# Power_noise.net
KiCad netlist of a schematic drawn in EAGLE
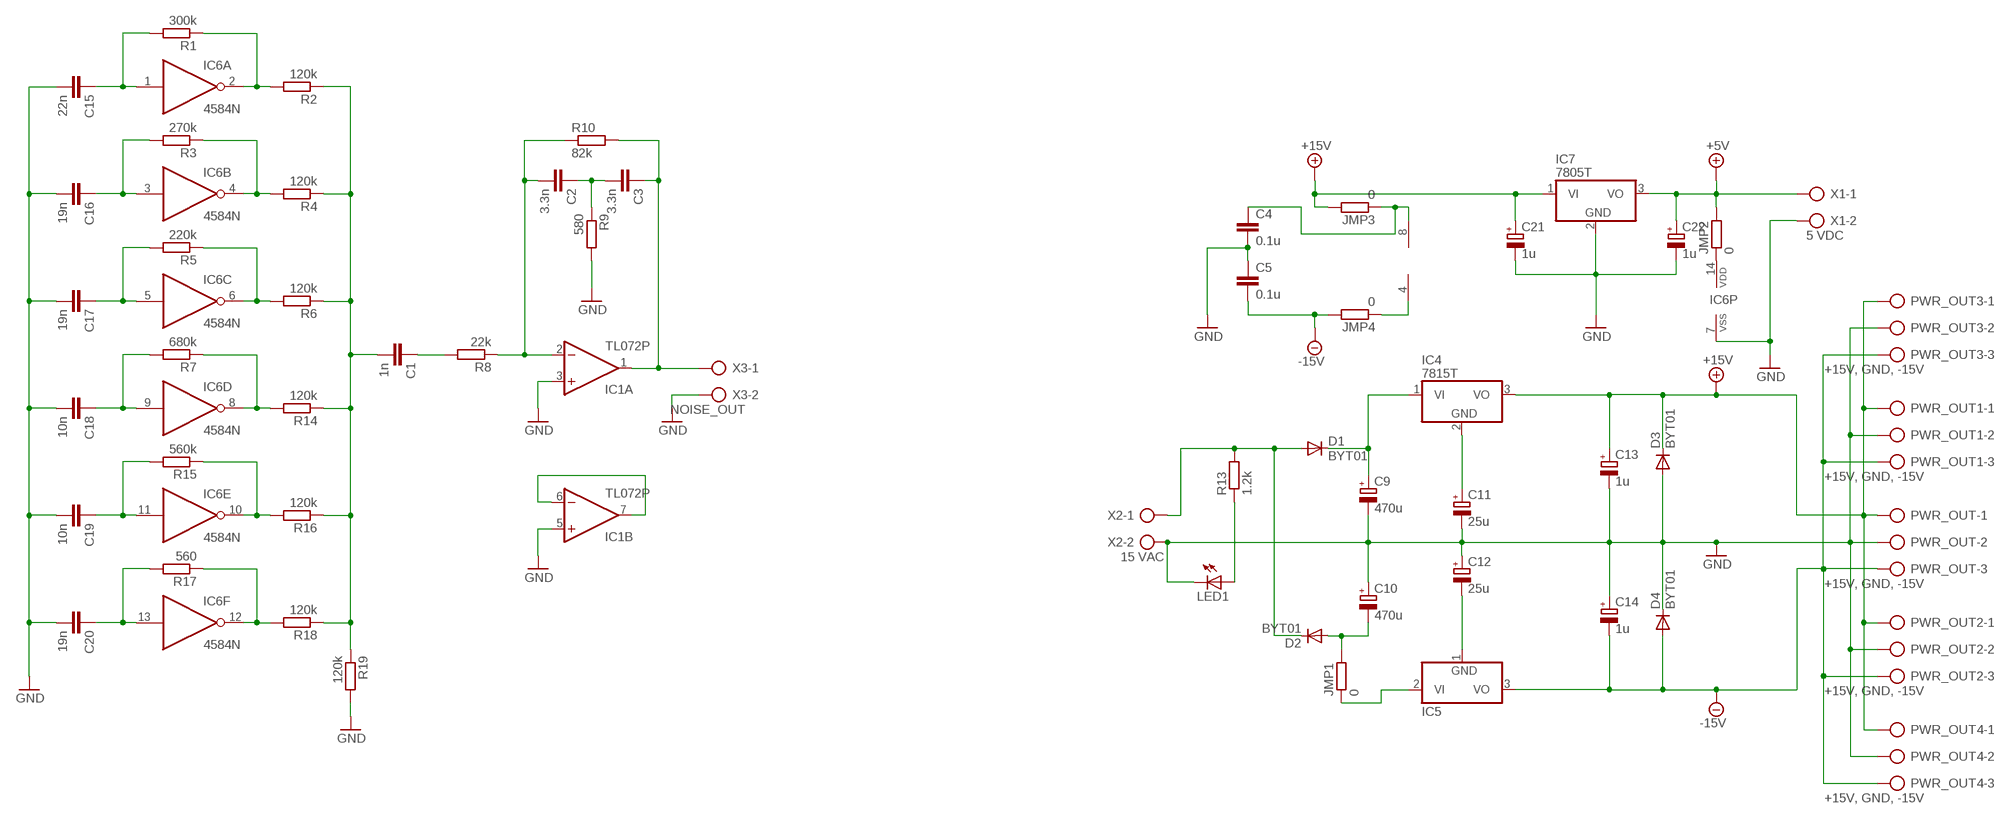
[diagram p0: schematic, sheet 1]

(export (version "E")
  (design (tool "Eeschema 10.0.6"))
  (components
    (comp (ref "C1")
      (value "1n")
      (footprint "eagle-import:C075-042X103")
      (libsource (lib "eagle-import") (part "C-EU075-042X103"))
    )
    (comp (ref "C2")
      (value "3.3n")
      (footprint "eagle-import:C075-042X103")
      (libsource (lib "eagle-import") (part "C-EU075-042X103"))
    )
    (comp (ref "C3")
      (value "3.3n")
      (footprint "eagle-import:C075-042X103")
      (libsource (lib "eagle-import") (part "C-EU075-042X103"))
    )
    (comp (ref "C4")
      (value "0.1u")
      (footprint "eagle-import:C075-042X103")
      (libsource (lib "eagle-import") (part "C-EU075-042X103"))
    )
    (comp (ref "C5")
      (value "0.1u")
      (footprint "eagle-import:C075-042X103")
      (libsource (lib "eagle-import") (part "C-EU075-042X103"))
    )
    (comp (ref "C9")
      (value "470u")
      (footprint "eagle-import:E5-6")
      (libsource (lib "eagle-import") (part "CPOL-EUE5-6"))
    )
    (comp (ref "C10")
      (value "470u")
      (footprint "eagle-import:E5-6")
      (libsource (lib "eagle-import") (part "CPOL-EUE5-6"))
    )
    (comp (ref "C11")
      (value "25u")
      (footprint "eagle-import:E5-6")
      (libsource (lib "eagle-import") (part "CPOL-EUE5-6"))
    )
    (comp (ref "C12")
      (value "25u")
      (footprint "eagle-import:E5-6")
      (libsource (lib "eagle-import") (part "CPOL-EUE5-6"))
    )
    (comp (ref "C13")
      (value "1u")
      (footprint "eagle-import:E5-6")
      (libsource (lib "eagle-import") (part "CPOL-EUE5-6"))
    )
    (comp (ref "C14")
      (value "1u")
      (footprint "eagle-import:E5-6")
      (libsource (lib "eagle-import") (part "CPOL-EUE5-6"))
    )
    (comp (ref "C15")
      (value "22n")
      (footprint "eagle-import:C075-042X103")
      (libsource (lib "eagle-import") (part "C-EU075-042X103"))
    )
    (comp (ref "C16")
      (value "19n")
      (footprint "eagle-import:C075-042X103")
      (libsource (lib "eagle-import") (part "C-EU075-042X103"))
    )
    (comp (ref "C17")
      (value "19n")
      (footprint "eagle-import:C075-042X103")
      (libsource (lib "eagle-import") (part "C-EU075-042X103"))
    )
    (comp (ref "C18")
      (value "10n")
      (footprint "eagle-import:C075-042X103")
      (libsource (lib "eagle-import") (part "C-EU075-042X103"))
    )
    (comp (ref "C19")
      (value "10n")
      (footprint "eagle-import:C075-042X103")
      (libsource (lib "eagle-import") (part "C-EU075-042X103"))
    )
    (comp (ref "C20")
      (value "19n")
      (footprint "eagle-import:C075-042X103")
      (libsource (lib "eagle-import") (part "C-EU075-042X103"))
    )
    (comp (ref "C21")
      (value "1u")
      (footprint "eagle-import:E5-6")
      (libsource (lib "eagle-import") (part "CPOL-EUE5-6"))
    )
    (comp (ref "C22")
      (value "1u")
      (footprint "eagle-import:E5-6")
      (libsource (lib "eagle-import") (part "CPOL-EUE5-6"))
    )
    (comp (ref "D1")
      (value "BYT01")
      (footprint "eagle-import:F126-10")
      (libsource (lib "eagle-import") (part "BYT01"))
    )
    (comp (ref "D2")
      (value "BYT01")
      (footprint "eagle-import:F126-10")
      (libsource (lib "eagle-import") (part "BYT01"))
    )
    (comp (ref "D3")
      (value "BYT01")
      (footprint "eagle-import:F126-10")
      (libsource (lib "eagle-import") (part "BYT01"))
    )
    (comp (ref "D4")
      (value "BYT01")
      (footprint "eagle-import:F126-10")
      (libsource (lib "eagle-import") (part "BYT01"))
    )
    (comp (ref "IC1")
      (value "TL072P")
      (footprint "eagle-import:DIL08")
      (libsource (lib "eagle-import") (part "TL072P"))
    )
    (comp (ref "IC4")
      (value "7815T")
      (footprint "eagle-import:TO220H")
      (libsource (lib "eagle-import") (part "78T15"))
    )
    (comp (ref "IC5")
      (value "7915T")
      (footprint "eagle-import:TO220H")
      (libsource (lib "eagle-import") (part "79T15"))
    )
    (comp (ref "IC6")
      (value "4584N")
      (footprint "eagle-import:DIL14")
      (libsource (lib "eagle-import") (part "4584N"))
    )
    (comp (ref "IC7")
      (value "7805T")
      (footprint "eagle-import:TO220H")
      (libsource (lib "eagle-import") (part "78T05"))
    )
    (comp (ref "JMP1")
      (value "0")
      (footprint "eagle-import:0207_10")
      (libsource (lib "eagle-import") (part "R-EU_0207/10"))
    )
    (comp (ref "JMP2")
      (value "0")
      (footprint "eagle-import:0207_10")
      (libsource (lib "eagle-import") (part "R-EU_0207/10"))
    )
    (comp (ref "JMP3")
      (value "0")
      (footprint "eagle-import:0207_12")
      (libsource (lib "eagle-import") (part "R-EU_0207/12"))
    )
    (comp (ref "JMP4")
      (value "0")
      (footprint "eagle-import:0207_10")
      (libsource (lib "eagle-import") (part "R-EU_0207/10"))
    )
    (comp (ref "LED1")
      (value "LED5MM")
      (footprint "eagle-import:LED5MM")
      (libsource (lib "eagle-import") (part "LED5MM"))
    )
    (comp (ref "PWR_OUT")
      (value "+15V, GND, -15V")
      (footprint "eagle-import:AK300_3")
      (libsource (lib "eagle-import") (part "AK300/3"))
    )
    (comp (ref "PWR_OUT1")
      (value "+15V, GND, -15V")
      (footprint "eagle-import:AK300_3")
      (libsource (lib "eagle-import") (part "AK300/3"))
    )
    (comp (ref "PWR_OUT2")
      (value "+15V, GND, -15V")
      (footprint "eagle-import:AK300_3")
      (libsource (lib "eagle-import") (part "AK300/3"))
    )
    (comp (ref "PWR_OUT3")
      (value "+15V, GND, -15V")
      (footprint "eagle-import:AK300_3")
      (libsource (lib "eagle-import") (part "AK300/3"))
    )
    (comp (ref "PWR_OUT4")
      (value "+15V, GND, -15V")
      (footprint "eagle-import:AK300_3")
      (libsource (lib "eagle-import") (part "AK300/3"))
    )
    (comp (ref "R1")
      (value "300k")
      (footprint "eagle-import:0207_5V")
      (libsource (lib "eagle-import") (part "R-EU_0207/5V"))
    )
    (comp (ref "R2")
      (value "120k")
      (footprint "eagle-import:0207_5V")
      (libsource (lib "eagle-import") (part "R-EU_0207/5V"))
    )
    (comp (ref "R3")
      (value "270k")
      (footprint "eagle-import:0207_5V")
      (libsource (lib "eagle-import") (part "R-EU_0207/5V"))
    )
    (comp (ref "R4")
      (value "120k")
      (footprint "eagle-import:0207_5V")
      (libsource (lib "eagle-import") (part "R-EU_0207/5V"))
    )
    (comp (ref "R5")
      (value "220k")
      (footprint "eagle-import:0207_5V")
      (libsource (lib "eagle-import") (part "R-EU_0207/5V"))
    )
    (comp (ref "R6")
      (value "120k")
      (footprint "eagle-import:0207_5V")
      (libsource (lib "eagle-import") (part "R-EU_0207/5V"))
    )
    (comp (ref "R7")
      (value "680k")
      (footprint "eagle-import:0207_5V")
      (libsource (lib "eagle-import") (part "R-EU_0207/5V"))
    )
    (comp (ref "R8")
      (value "22k")
      (footprint "eagle-import:0207_5V")
      (libsource (lib "eagle-import") (part "R-EU_0207/5V"))
    )
    (comp (ref "R9")
      (value "580")
      (footprint "eagle-import:0207_5V")
      (libsource (lib "eagle-import") (part "R-EU_0207/5V"))
    )
    (comp (ref "R10")
      (value "82k")
      (footprint "eagle-import:0207_5V")
      (libsource (lib "eagle-import") (part "R-EU_0207/5V"))
    )
    (comp (ref "R13")
      (value "1.2k")
      (footprint "eagle-import:0207_5V")
      (libsource (lib "eagle-import") (part "R-EU_0207/5V"))
    )
    (comp (ref "R14")
      (value "120k")
      (footprint "eagle-import:0207_5V")
      (libsource (lib "eagle-import") (part "R-EU_0207/5V"))
    )
    (comp (ref "R15")
      (value "560k")
      (footprint "eagle-import:0207_5V")
      (libsource (lib "eagle-import") (part "R-EU_0207/5V"))
    )
    (comp (ref "R16")
      (value "120k")
      (footprint "eagle-import:0207_5V")
      (libsource (lib "eagle-import") (part "R-EU_0207/5V"))
    )
    (comp (ref "R17")
      (value "560")
      (footprint "eagle-import:0207_5V")
      (libsource (lib "eagle-import") (part "R-EU_0207/5V"))
    )
    (comp (ref "R18")
      (value "120k")
      (footprint "eagle-import:0207_5V")
      (libsource (lib "eagle-import") (part "R-EU_0207/5V"))
    )
    (comp (ref "R19")
      (value "120k")
      (footprint "eagle-import:0207_5V")
      (libsource (lib "eagle-import") (part "R-EU_0207/5V"))
    )
    (comp (ref "X1")
      (value "5 VDC")
      (footprint "eagle-import:AK300_2")
      (libsource (lib "eagle-import") (part "AK300/2"))
    )
    (comp (ref "X2")
      (value "15 VAC")
      (footprint "eagle-import:AK300_2")
      (libsource (lib "eagle-import") (part "AK300/2"))
    )
    (comp (ref "X3")
      (value "NOISE_OUT")
      (footprint "eagle-import:AK300_2")
      (libsource (lib "eagle-import") (part "AK300/2"))
    )
  )
  (nets
    (net (code "1") (name "+5V") (class "Default")
      (node (ref "C22") (pin "+") (pinfunction "+_+") (pintype "passive"))
      (node (ref "IC7") (pin "3") (pinfunction "VO_3") (pintype "passive"))
      (node (ref "JMP2") (pin "2") (pinfunction "2_2") (pintype "passive"))
      (node (ref "X1") (pin "1") (pinfunction "KL_1") (pintype "passive"))
    )
    (net (code "2") (name "+15V") (class "Default")
      (node (ref "C13") (pin "+") (pinfunction "+_+") (pintype "passive"))
      (node (ref "C21") (pin "+") (pinfunction "+_+") (pintype "passive"))
      (node (ref "D3") (pin "C") (pinfunction "C_C") (pintype "passive"))
      (node (ref "IC4") (pin "3") (pinfunction "VO_3") (pintype "passive"))
      (node (ref "IC7") (pin "1") (pinfunction "VI_1") (pintype "input"))
      (node (ref "JMP3") (pin "2") (pinfunction "2_2") (pintype "passive"))
      (node (ref "PWR_OUT") (pin "1") (pinfunction "KL_1") (pintype "passive"))
      (node (ref "PWR_OUT1") (pin "1") (pinfunction "KL_1") (pintype "passive"))
      (node (ref "PWR_OUT2") (pin "1") (pinfunction "KL_1") (pintype "passive"))
      (node (ref "PWR_OUT3") (pin "1") (pinfunction "KL_1") (pintype "passive"))
      (node (ref "PWR_OUT4") (pin "1") (pinfunction "KL_1") (pintype "passive"))
    )
    (net (code "3") (name "-15V") (class "Default")
      (node (ref "C14") (pin "-") (pinfunction "-_-") (pintype "passive"))
      (node (ref "C5") (pin "2") (pinfunction "2_2") (pintype "passive"))
      (node (ref "D4") (pin "A") (pinfunction "A_A") (pintype "passive"))
      (node (ref "IC5") (pin "3") (pinfunction "VO_3") (pintype "passive"))
      (node (ref "JMP4") (pin "2") (pinfunction "2_2") (pintype "passive"))
      (node (ref "PWR_OUT") (pin "3") (pinfunction "KL_3") (pintype "passive"))
      (node (ref "PWR_OUT1") (pin "3") (pinfunction "KL_3") (pintype "passive"))
      (node (ref "PWR_OUT2") (pin "3") (pinfunction "KL_3") (pintype "passive"))
      (node (ref "PWR_OUT3") (pin "3") (pinfunction "KL_3") (pintype "passive"))
      (node (ref "PWR_OUT4") (pin "3") (pinfunction "KL_3") (pintype "passive"))
    )
    (net (code "4") (name "GND") (class "Default")
      (node (ref "C10") (pin "+") (pinfunction "+_+") (pintype "passive"))
      (node (ref "C11") (pin "-") (pinfunction "-_-") (pintype "passive"))
      (node (ref "C12") (pin "+") (pinfunction "+_+") (pintype "passive"))
      (node (ref "C13") (pin "-") (pinfunction "-_-") (pintype "passive"))
      (node (ref "C14") (pin "+") (pinfunction "+_+") (pintype "passive"))
      (node (ref "C15") (pin "2") (pinfunction "2_2") (pintype "passive"))
      (node (ref "C16") (pin "2") (pinfunction "2_2") (pintype "passive"))
      (node (ref "C17") (pin "2") (pinfunction "2_2") (pintype "passive"))
      (node (ref "C18") (pin "2") (pinfunction "2_2") (pintype "passive"))
      (node (ref "C19") (pin "2") (pinfunction "2_2") (pintype "passive"))
      (node (ref "C20") (pin "2") (pinfunction "2_2") (pintype "passive"))
      (node (ref "C21") (pin "-") (pinfunction "-_-") (pintype "passive"))
      (node (ref "C22") (pin "-") (pinfunction "-_-") (pintype "passive"))
      (node (ref "C4") (pin "2") (pinfunction "2_2") (pintype "passive"))
      (node (ref "C5") (pin "1") (pinfunction "1_1") (pintype "passive"))
      (node (ref "C9") (pin "-") (pinfunction "-_-") (pintype "passive"))
      (node (ref "D3") (pin "A") (pinfunction "A_A") (pintype "passive"))
      (node (ref "D4") (pin "C") (pinfunction "C_C") (pintype "passive"))
      (node (ref "IC1") (pin "3") (pinfunction "+IN_3") (pintype "input"))
      (node (ref "IC1") (pin "5") (pinfunction "+IN_5") (pintype "input"))
      (node (ref "IC6") (pin "7") (pinfunction "VSS_7") (pintype "power_in"))
      (node (ref "IC7") (pin "2") (pinfunction "GND_2") (pintype "passive"))
      (node (ref "LED1") (pin "K") (pinfunction "C_K") (pintype "passive"))
      (node (ref "PWR_OUT") (pin "2") (pinfunction "KL_2") (pintype "passive"))
      (node (ref "PWR_OUT1") (pin "2") (pinfunction "KL_2") (pintype "passive"))
      (node (ref "PWR_OUT2") (pin "2") (pinfunction "KL_2") (pintype "passive"))
      (node (ref "PWR_OUT3") (pin "2") (pinfunction "KL_2") (pintype "passive"))
      (node (ref "PWR_OUT4") (pin "2") (pinfunction "KL_2") (pintype "passive"))
      (node (ref "R19") (pin "2") (pinfunction "2_2") (pintype "passive"))
      (node (ref "R9") (pin "2") (pinfunction "2_2") (pintype "passive"))
      (node (ref "X1") (pin "2") (pinfunction "KL_2") (pintype "passive"))
      (node (ref "X2") (pin "2") (pinfunction "KL_2") (pintype "passive"))
      (node (ref "X3") (pin "2") (pinfunction "KL_2") (pintype "passive"))
    )
    (net (code "5") (name "Net-(C1-Pad1)") (class "Default")
      (node (ref "C1") (pin "1") (pinfunction "1_1") (pintype "passive"))
      (node (ref "R8") (pin "2") (pinfunction "2_2") (pintype "passive"))
    )
    (net (code "6") (name "Net-(C1-Pad2)") (class "Default")
      (node (ref "C1") (pin "2") (pinfunction "2_2") (pintype "passive"))
      (node (ref "R14") (pin "1") (pinfunction "1_1") (pintype "passive"))
      (node (ref "R16") (pin "1") (pinfunction "1_1") (pintype "passive"))
      (node (ref "R18") (pin "1") (pinfunction "1_1") (pintype "passive"))
      (node (ref "R19") (pin "1") (pinfunction "1_1") (pintype "passive"))
      (node (ref "R2") (pin "1") (pinfunction "1_1") (pintype "passive"))
      (node (ref "R4") (pin "1") (pinfunction "1_1") (pintype "passive"))
      (node (ref "R6") (pin "1") (pinfunction "1_1") (pintype "passive"))
    )
    (net (code "7") (name "Net-(C2-Pad1)") (class "Default")
      (node (ref "C2") (pin "1") (pinfunction "1_1") (pintype "passive"))
      (node (ref "C3") (pin "2") (pinfunction "2_2") (pintype "passive"))
      (node (ref "R9") (pin "1") (pinfunction "1_1") (pintype "passive"))
    )
    (net (code "8") (name "Net-(C10-Pad-)") (class "Default")
      (node (ref "C10") (pin "-") (pinfunction "-_-") (pintype "passive"))
      (node (ref "D2") (pin "A") (pinfunction "A_A") (pintype "passive"))
      (node (ref "JMP1") (pin "2") (pinfunction "2_2") (pintype "passive"))
    )
    (net (code "9") (name "Net-(IC1A--IN)") (class "Default")
      (node (ref "C2") (pin "2") (pinfunction "2_2") (pintype "passive"))
      (node (ref "IC1") (pin "2") (pinfunction "-IN_2") (pintype "input"))
      (node (ref "R10") (pin "1") (pinfunction "1_1") (pintype "passive"))
      (node (ref "R8") (pin "1") (pinfunction "1_1") (pintype "passive"))
    )
    (net (code "10") (name "Net-(IC1A-OUT)") (class "Default")
      (node (ref "C3") (pin "1") (pinfunction "1_1") (pintype "passive"))
      (node (ref "IC1") (pin "1") (pinfunction "OUT_1") (pintype "output"))
      (node (ref "R10") (pin "2") (pinfunction "2_2") (pintype "passive"))
      (node (ref "X3") (pin "1") (pinfunction "KL_1") (pintype "passive"))
    )
    (net (code "11") (name "Net-(IC1B--IN)") (class "Default")
      (node (ref "IC1") (pin "6") (pinfunction "-IN_6") (pintype "input"))
      (node (ref "IC1") (pin "7") (pinfunction "OUT_7") (pintype "output"))
    )
    (net (code "12") (name "Net-(IC1C-V+)") (class "Default")
      (node (ref "C4") (pin "1") (pinfunction "1_1") (pintype "passive"))
      (node (ref "IC1") (pin "8") (pinfunction "V+_8") (pintype "power_in"))
      (node (ref "JMP3") (pin "1") (pinfunction "1_1") (pintype "passive"))
    )
    (net (code "13") (name "Net-(IC1C-V-)") (class "Default")
      (node (ref "IC1") (pin "4") (pinfunction "V-_4") (pintype "power_in"))
      (node (ref "JMP4") (pin "1") (pinfunction "1_1") (pintype "passive"))
    )
    (net (code "14") (name "Net-(IC4-GND)") (class "Default")
      (node (ref "C11") (pin "+") (pinfunction "+_+") (pintype "passive"))
      (node (ref "IC4") (pin "2") (pinfunction "GND_2") (pintype "passive"))
    )
    (net (code "15") (name "Net-(IC4-VI)") (class "Default")
      (node (ref "C9") (pin "+") (pinfunction "+_+") (pintype "passive"))
      (node (ref "D1") (pin "C") (pinfunction "C_C") (pintype "passive"))
      (node (ref "IC4") (pin "1") (pinfunction "VI_1") (pintype "input"))
    )
    (net (code "16") (name "Net-(IC5-GND)") (class "Default")
      (node (ref "C12") (pin "-") (pinfunction "-_-") (pintype "passive"))
      (node (ref "IC5") (pin "1") (pinfunction "GND_1") (pintype "passive"))
    )
    (net (code "17") (name "Net-(IC5-VI)") (class "Default")
      (node (ref "IC5") (pin "2") (pinfunction "VI_2") (pintype "input"))
      (node (ref "JMP1") (pin "1") (pinfunction "1_1") (pintype "passive"))
    )
    (net (code "18") (name "Net-(IC6A-I)") (class "Default")
      (node (ref "C15") (pin "1") (pinfunction "1_1") (pintype "passive"))
      (node (ref "IC6") (pin "1") (pinfunction "I_1") (pintype "input"))
      (node (ref "R1") (pin "2") (pinfunction "2_2") (pintype "passive"))
    )
    (net (code "19") (name "Net-(IC6A-O)") (class "Default")
      (node (ref "IC6") (pin "2") (pinfunction "O_2") (pintype "output"))
      (node (ref "R1") (pin "1") (pinfunction "1_1") (pintype "passive"))
      (node (ref "R2") (pin "2") (pinfunction "2_2") (pintype "passive"))
    )
    (net (code "20") (name "Net-(IC6B-I)") (class "Default")
      (node (ref "C16") (pin "1") (pinfunction "1_1") (pintype "passive"))
      (node (ref "IC6") (pin "3") (pinfunction "I_3") (pintype "input"))
      (node (ref "R3") (pin "2") (pinfunction "2_2") (pintype "passive"))
    )
    (net (code "21") (name "Net-(IC6B-O)") (class "Default")
      (node (ref "IC6") (pin "4") (pinfunction "O_4") (pintype "output"))
      (node (ref "R3") (pin "1") (pinfunction "1_1") (pintype "passive"))
      (node (ref "R4") (pin "2") (pinfunction "2_2") (pintype "passive"))
    )
    (net (code "22") (name "Net-(IC6C-I)") (class "Default")
      (node (ref "C17") (pin "1") (pinfunction "1_1") (pintype "passive"))
      (node (ref "IC6") (pin "5") (pinfunction "I_5") (pintype "input"))
      (node (ref "R5") (pin "2") (pinfunction "2_2") (pintype "passive"))
    )
    (net (code "23") (name "Net-(IC6C-O)") (class "Default")
      (node (ref "IC6") (pin "6") (pinfunction "O_6") (pintype "output"))
      (node (ref "R5") (pin "1") (pinfunction "1_1") (pintype "passive"))
      (node (ref "R6") (pin "2") (pinfunction "2_2") (pintype "passive"))
    )
    (net (code "24") (name "Net-(IC6D-I)") (class "Default")
      (node (ref "C18") (pin "1") (pinfunction "1_1") (pintype "passive"))
      (node (ref "IC6") (pin "9") (pinfunction "I_9") (pintype "input"))
      (node (ref "R7") (pin "2") (pinfunction "2_2") (pintype "passive"))
    )
    (net (code "25") (name "Net-(IC6D-O)") (class "Default")
      (node (ref "IC6") (pin "8") (pinfunction "O_8") (pintype "output"))
      (node (ref "R14") (pin "2") (pinfunction "2_2") (pintype "passive"))
      (node (ref "R7") (pin "1") (pinfunction "1_1") (pintype "passive"))
    )
    (net (code "26") (name "Net-(IC6E-I)") (class "Default")
      (node (ref "C19") (pin "1") (pinfunction "1_1") (pintype "passive"))
      (node (ref "IC6") (pin "11") (pinfunction "I_11") (pintype "input"))
      (node (ref "R15") (pin "2") (pinfunction "2_2") (pintype "passive"))
    )
    (net (code "27") (name "Net-(IC6E-O)") (class "Default")
      (node (ref "IC6") (pin "10") (pinfunction "O_10") (pintype "output"))
      (node (ref "R15") (pin "1") (pinfunction "1_1") (pintype "passive"))
      (node (ref "R16") (pin "2") (pinfunction "2_2") (pintype "passive"))
    )
    (net (code "28") (name "Net-(IC6F-I)") (class "Default")
      (node (ref "C20") (pin "1") (pinfunction "1_1") (pintype "passive"))
      (node (ref "IC6") (pin "13") (pinfunction "I_13") (pintype "input"))
      (node (ref "R17") (pin "2") (pinfunction "2_2") (pintype "passive"))
    )
    (net (code "29") (name "Net-(IC6F-O)") (class "Default")
      (node (ref "IC6") (pin "12") (pinfunction "O_12") (pintype "output"))
      (node (ref "R17") (pin "1") (pinfunction "1_1") (pintype "passive"))
      (node (ref "R18") (pin "2") (pinfunction "2_2") (pintype "passive"))
    )
    (net (code "30") (name "Net-(IC6G-VDD)") (class "Default")
      (node (ref "IC6") (pin "14") (pinfunction "VDD_14") (pintype "power_in"))
      (node (ref "JMP2") (pin "1") (pinfunction "1_1") (pintype "passive"))
    )
    (net (code "31") (name "Net-(LED1-PadA)") (class "Default")
      (node (ref "LED1") (pin "A") (pinfunction "A_A") (pintype "passive"))
      (node (ref "R13") (pin "1") (pinfunction "1_1") (pintype "passive"))
    )
    (net (code "32") (name "Net-(X2A-KL)") (class "Default")
      (node (ref "D1") (pin "A") (pinfunction "A_A") (pintype "passive"))
      (node (ref "D2") (pin "C") (pinfunction "C_C") (pintype "passive"))
      (node (ref "R13") (pin "2") (pinfunction "2_2") (pintype "passive"))
      (node (ref "X2") (pin "1") (pinfunction "KL_1") (pintype "passive"))
    )
  )
)
